# Gecko.net
KiCad netlist of a schematic drawn in Altium Designer
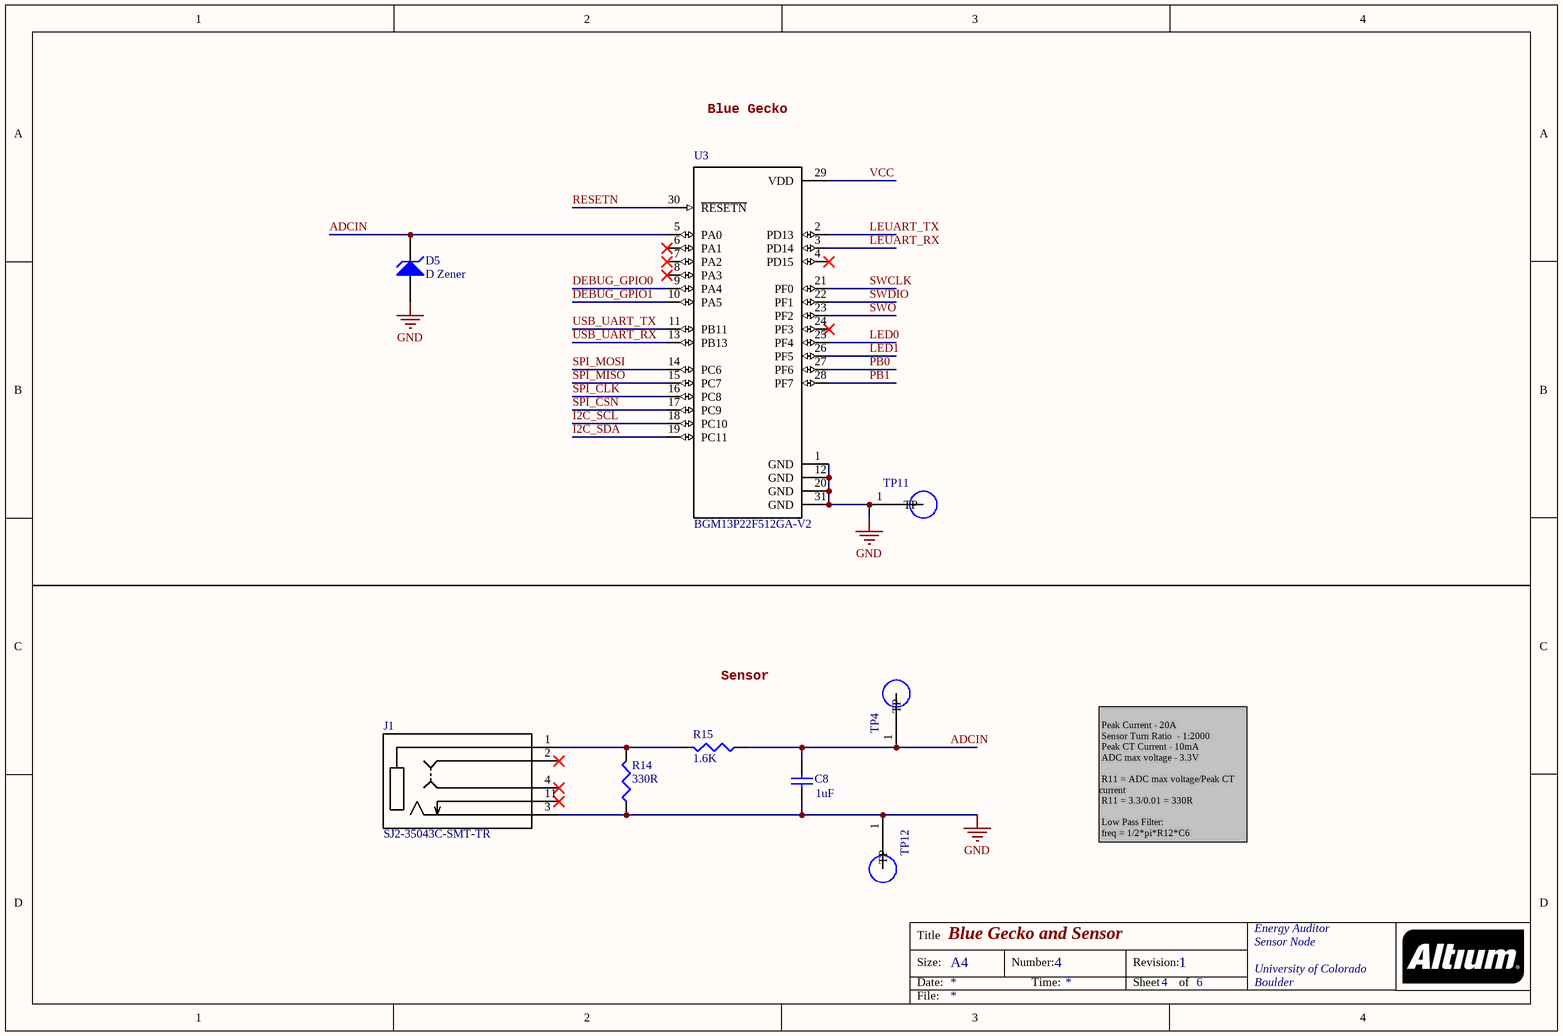
[diagram p0: Gecko.SchDoc]

(export (version "E")
  (design (tool "Eeschema 10.0.6"))
  (components
    (comp (ref "C8")
      (value "1uF")
      (footprint "1608[0603]")
      (description "CAP CER 1UF 16V X7R 0603")
      (fields
        (field (name "DIGI-KEY PART NUMBER") "1276-6524-1-ND")
        (field (name "MANUFACTURER") "Samsung Electro-Mechanics")
      )
      (libsource (lib "Miscellaneous Devices") (part "Cap"))
    )
    (comp (ref "D5")
      (value "D Zener")
      (footprint "0402")
      (description "Zener Diode")
      (fields
        (field (name "MANUFACTURER PART NUMBER") "TPD1E10B06DPYR")
        (field (name "DIGI-KEY PART NUMBER") "296-30406-1-ND")
      )
      (libsource (lib "Miscellaneous Devices") (part "D Zener"))
    )
    (comp (ref "J1")
      (value "SJ2-35043C-SMT-TR")
      (footprint "CUI_SJ2-35043C-SMT-TR")
      (description "AUDIO JACK, 3.5 MM, RT, 4 CONDUC")
      (fields
        (field (name "DIGI-KEY PART NUMBER") "CP-SJ2-35043C-SMT-CT-ND")
        (field (name "MANUFACTURER") "CUI Inc.")
      )
      (libsource (lib "SJ2-35043C-SMT-TR") (part "SJ2-35043C-SMT-TR"))
    )
    (comp (ref "R14")
      (value "330R")
      (footprint "1608[0603]")
      (description "RES SMD 330 OHM 5% 1/10W 0603")
      (fields
        (field (name "DIGI-KEY PART NUMBER") "541-4060-1-ND")
        (field (name "MANUFACTURER") "Vishay Dale")
      )
      (libsource (lib "Miscellaneous Devices") (part "Res3"))
    )
    (comp (ref "R15")
      (value "1.6K")
      (footprint "1608[0603]")
      (description "RES SMD 1.6K OHM 5% 1/10W 0603")
      (fields (field (name "DIGI-KEY PART NUMBER") "311-1.6KGRCT-ND") (field (name "MANUFACTURER") "Yageo"))
      (libsource (lib "Miscellaneous Devices") (part "Res3"))
    )
    (comp (ref "TP4")
      (value "5019")
      (footprint "TP380X203")
      (description "Phosphor Bronze Contact Miniature Silver Plated Surface Mount Test Points")
      (fields (field (name "DIGI-KEY PART NUMBER") "36-5019CT-ND") (field (name "MANUFACTURER") "Keystone"))
      (libsource (lib "5019") (part "5019"))
    )
    (comp (ref "TP11")
      (value "5019")
      (footprint "TP380X203")
      (description "Phosphor Bronze Contact Miniature Silver Plated Surface Mount Test Points")
      (fields (field (name "DIGI-KEY PART NUMBER") "36-5019CT-ND") (field (name "MANUFACTURER") "Keystone"))
      (libsource (lib "5019") (part "5019"))
    )
    (comp (ref "TP12")
      (value "5019")
      (footprint "TP380X203")
      (description "Phosphor Bronze Contact Miniature Silver Plated Surface Mount Test Points")
      (fields (field (name "DIGI-KEY PART NUMBER") "36-5019CT-ND") (field (name "MANUFACTURER") "Keystone"))
      (libsource (lib "5019") (part "5019"))
    )
    (comp (ref "U3")
      (value "BGM13P22F512GA-V2")
      (footprint "MODULE_BGM13P22F512GA-V2")
      (description "BLUETOOTH 5.0 MODULE")
      (fields
        (field (name "MANUFACTURER") "Silicon Labs")
        (field (name "DIGI-KEY PART NUMBER") "336-5146-1-ND")
      )
      (libsource (lib "BGM13P22F512GA-V2") (part "BGM13P22F512GA-V2"))
    )
  )
  (nets
    (net (code "1") (name "/ADCIN") (class "Default")
      (node (ref "C8") (pin "2") (pinfunction "2_2") (pintype "passive"))
      (node (ref "D5") (pin "2") (pinfunction "K_2") (pintype "passive"))
      (node (ref "R15") (pin "1") (pinfunction "1_1") (pintype "passive"))
      (node (ref "TP4") (pin "1") (pinfunction "TP_1") (pintype "passive"))
      (node (ref "U3") (pin "5") (pinfunction "PA0_5") (pintype "bidirectional"))
    )
    (net (code "2") (name "/DEBUG_GPIO0") (class "Default")
      (node (ref "U3") (pin "9") (pinfunction "PA4_9") (pintype "bidirectional"))
    )
    (net (code "3") (name "/DEBUG_GPIO1") (class "Default")
      (node (ref "U3") (pin "10") (pinfunction "PA5_10") (pintype "bidirectional"))
    )
    (net (code "4") (name "/I2C_SCL") (class "Default")
      (node (ref "U3") (pin "18") (pinfunction "PC10_18") (pintype "bidirectional"))
    )
    (net (code "5") (name "/I2C_SDA") (class "Default")
      (node (ref "U3") (pin "19") (pinfunction "PC11_19") (pintype "bidirectional"))
    )
    (net (code "6") (name "/LED0") (class "Default")
      (node (ref "U3") (pin "25") (pinfunction "PF4_25") (pintype "bidirectional"))
    )
    (net (code "7") (name "/LED1") (class "Default")
      (node (ref "U3") (pin "26") (pinfunction "PF5_26") (pintype "bidirectional"))
    )
    (net (code "8") (name "/LEUART_RX") (class "Default")
      (node (ref "U3") (pin "3") (pinfunction "PD14_3") (pintype "bidirectional"))
    )
    (net (code "9") (name "/LEUART_TX") (class "Default")
      (node (ref "U3") (pin "2") (pinfunction "PD13_2") (pintype "bidirectional"))
    )
    (net (code "10") (name "/PB0") (class "Default")
      (node (ref "U3") (pin "27") (pinfunction "PF6_27") (pintype "bidirectional"))
    )
    (net (code "11") (name "/PB1") (class "Default")
      (node (ref "U3") (pin "28") (pinfunction "PF7_28") (pintype "bidirectional"))
    )
    (net (code "12") (name "/RESETN") (class "Default")
      (node (ref "U3") (pin "30") (pinfunction "~{RESETN}_30") (pintype "input"))
    )
    (net (code "13") (name "/SPI_CLK") (class "Default")
      (node (ref "U3") (pin "16") (pinfunction "PC8_16") (pintype "bidirectional"))
    )
    (net (code "14") (name "/SPI_CSN") (class "Default")
      (node (ref "U3") (pin "17") (pinfunction "PC9_17") (pintype "bidirectional"))
    )
    (net (code "15") (name "/SPI_MISO") (class "Default")
      (node (ref "U3") (pin "15") (pinfunction "PC7_15") (pintype "bidirectional"))
    )
    (net (code "16") (name "/SPI_MOSI") (class "Default")
      (node (ref "U3") (pin "14") (pinfunction "PC6_14") (pintype "bidirectional"))
    )
    (net (code "17") (name "/SWCLK") (class "Default")
      (node (ref "U3") (pin "21") (pinfunction "PF0_21") (pintype "bidirectional"))
    )
    (net (code "18") (name "/SWDIO") (class "Default")
      (node (ref "U3") (pin "22") (pinfunction "PF1_22") (pintype "bidirectional"))
    )
    (net (code "19") (name "/SWO") (class "Default")
      (node (ref "U3") (pin "23") (pinfunction "PF2_23") (pintype "bidirectional"))
    )
    (net (code "20") (name "/USB_UART_RX") (class "Default")
      (node (ref "U3") (pin "13") (pinfunction "PB13_13") (pintype "bidirectional"))
    )
    (net (code "21") (name "/USB_UART_TX") (class "Default")
      (node (ref "U3") (pin "11") (pinfunction "PB11_11") (pintype "bidirectional"))
    )
    (net (code "22") (name "/VCC") (class "Default")
      (node (ref "U3") (pin "29") (pinfunction "VDD_29") (pintype "power_in"))
    )
    (net (code "23") (name "GND") (class "Default")
      (node (ref "C8") (pin "1") (pinfunction "1_1") (pintype "passive"))
      (node (ref "D5") (pin "1") (pinfunction "A_1") (pintype "passive"))
      (node (ref "J1") (pin "3") (pinfunction "RING_3") (pintype "passive"))
      (node (ref "R14") (pin "1") (pinfunction "1_1") (pintype "passive"))
      (node (ref "TP11") (pin "1") (pinfunction "TP_1") (pintype "passive"))
      (node (ref "TP12") (pin "1") (pinfunction "TP_1") (pintype "passive"))
      (node (ref "U3") (pin "1") (pinfunction "GND_1") (pintype "power_in"))
      (node (ref "U3") (pin "12") (pinfunction "GND_12") (pintype "power_in"))
      (node (ref "U3") (pin "20") (pinfunction "GND_20") (pintype "power_in"))
      (node (ref "U3") (pin "31") (pinfunction "GND_31") (pintype "power_in"))
    )
    (net (code "24") (name "Net-(J1-SLEEVE)") (class "Default")
      (node (ref "J1") (pin "1") (pinfunction "SLEEVE_1") (pintype "passive"))
      (node (ref "R14") (pin "2") (pinfunction "2_2") (pintype "passive"))
      (node (ref "R15") (pin "2") (pinfunction "2_2") (pintype "passive"))
    )
    (net (code "25") (name "unconnected-(J1-RING_SWITCH-Pad11)") (class "Default")
      (node (ref "J1") (pin "11") (pinfunction "RING_SWITCH_11") (pintype "passive+no_connect"))
    )
    (net (code "26") (name "unconnected-(J1-TIP_1-Pad2)") (class "Default")
      (node (ref "J1") (pin "2") (pinfunction "TIP_1_2") (pintype "passive+no_connect"))
    )
    (net (code "27") (name "unconnected-(J1-TIP_2-Pad4)") (class "Default")
      (node (ref "J1") (pin "4") (pinfunction "TIP_2_4") (pintype "passive+no_connect"))
    )
    (net (code "28") (name "unconnected-(U3-PA1-Pad6)") (class "Default")
      (node (ref "U3") (pin "6") (pinfunction "PA1_6") (pintype "bidirectional+no_connect"))
    )
    (net (code "29") (name "unconnected-(U3-PA2-Pad7)") (class "Default")
      (node (ref "U3") (pin "7") (pinfunction "PA2_7") (pintype "bidirectional+no_connect"))
    )
    (net (code "30") (name "unconnected-(U3-PA3-Pad8)") (class "Default")
      (node (ref "U3") (pin "8") (pinfunction "PA3_8") (pintype "bidirectional+no_connect"))
    )
    (net (code "31") (name "unconnected-(U3-PD15-Pad4)") (class "Default")
      (node (ref "U3") (pin "4") (pinfunction "PD15_4") (pintype "bidirectional+no_connect"))
    )
    (net (code "32") (name "unconnected-(U3-PF3-Pad24)") (class "Default")
      (node (ref "U3") (pin "24") (pinfunction "PF3_24") (pintype "bidirectional+no_connect"))
    )
  )
)
